# Motor_Double_Board.net
KiCad netlist of a schematic drawn in EAGLE
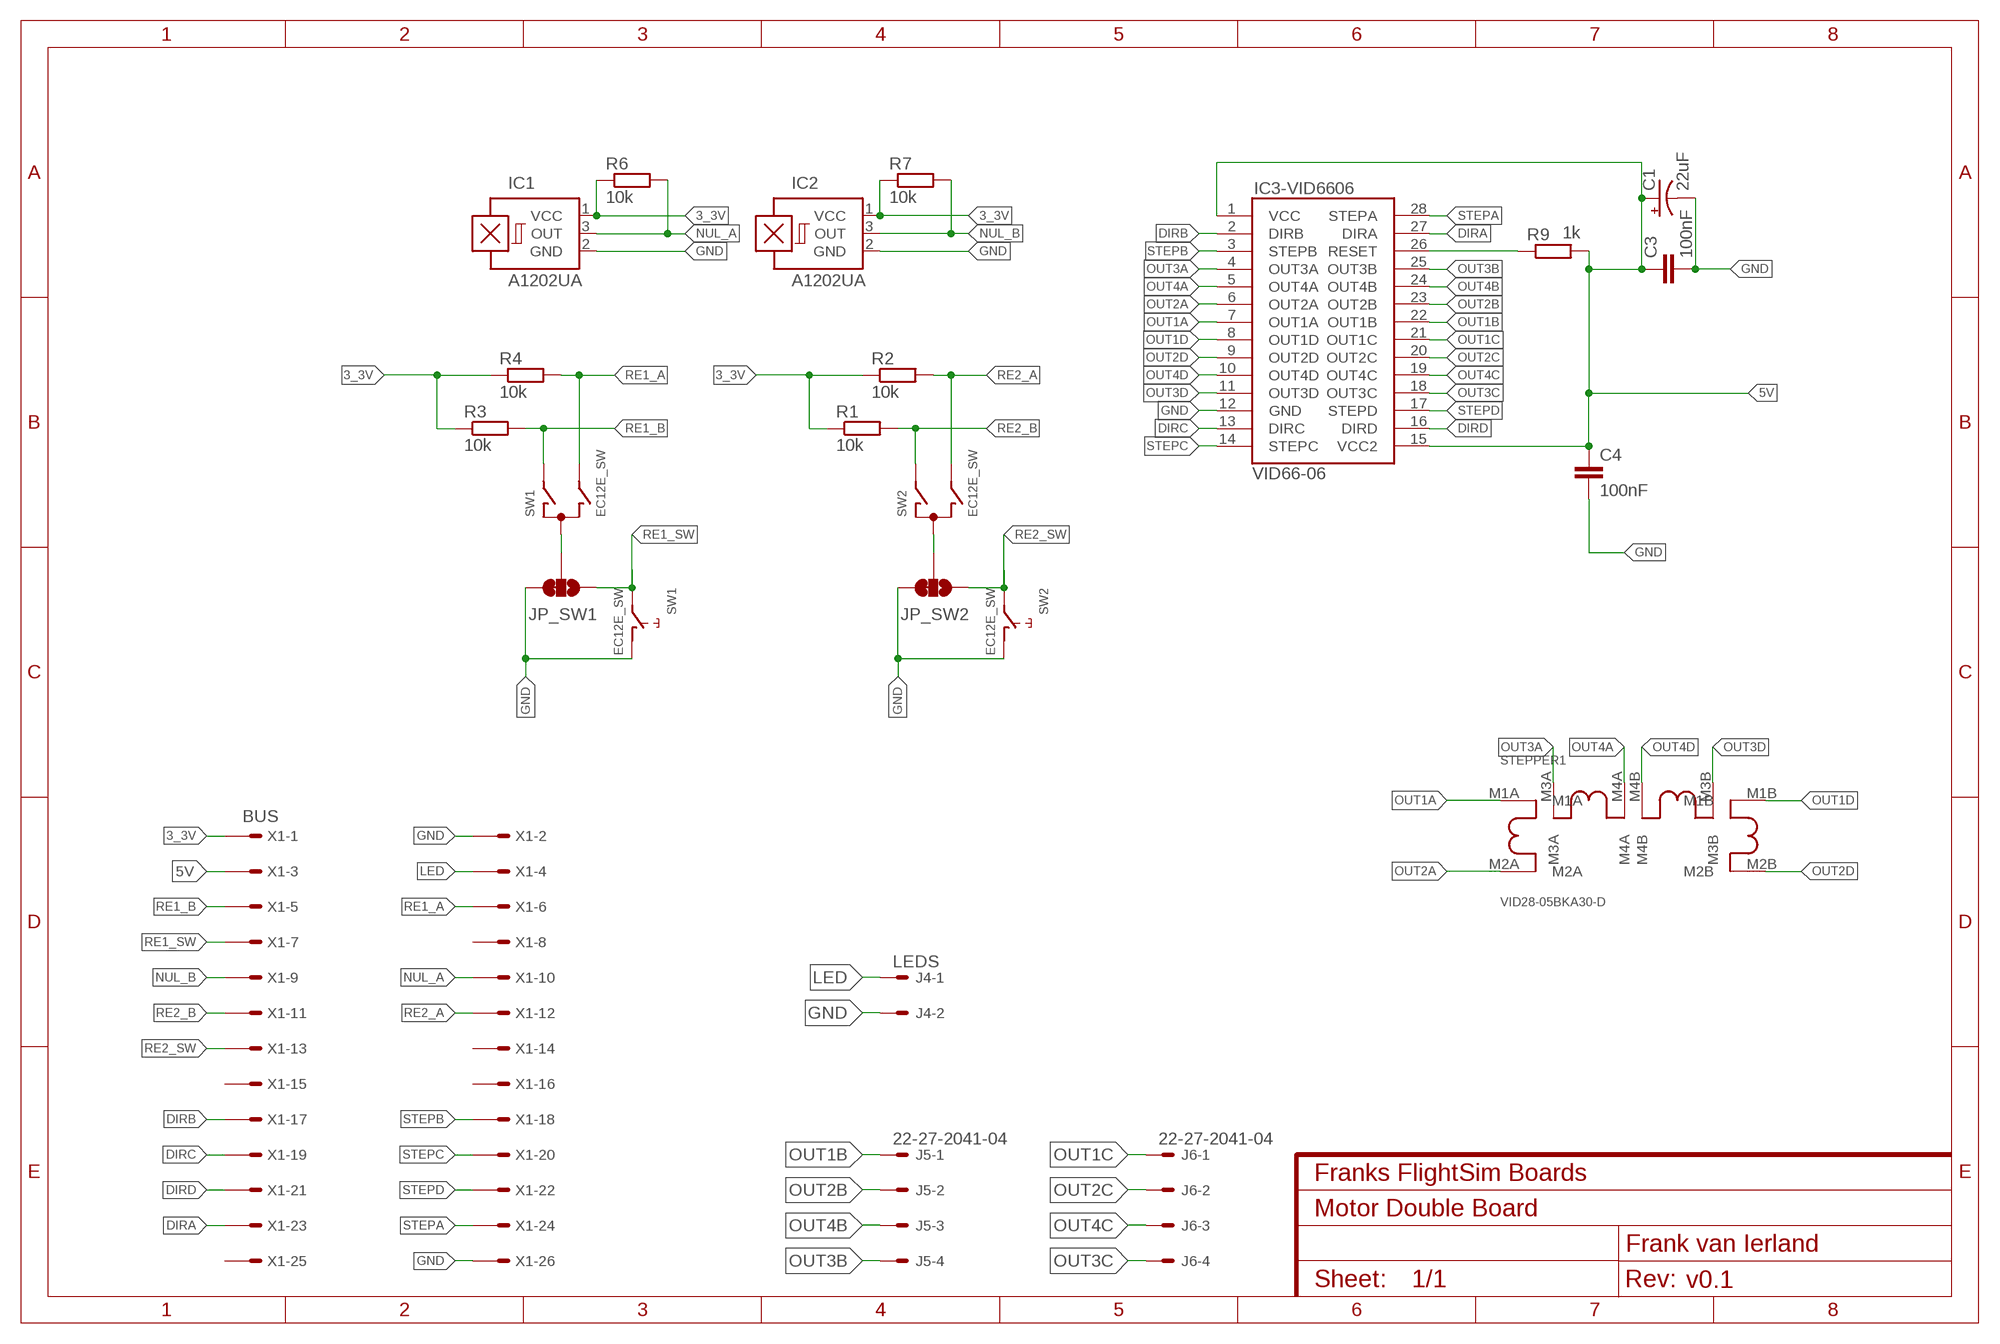
[diagram p0: schematic, sheet 1]

(export (version "E")
  (design (tool "Eeschema 10.0.6"))
  (components
    (comp (ref "C1")
      (value "22uF")
      (footprint "eagle-import:PANASONIC_C")
      (libsource (lib "eagle-import") (part "22UF-POLAR-PANASONIC_C-35V-20%"))
    )
    (comp (ref "C3")
      (value "100nF")
      (footprint "eagle-import:C0805")
      (libsource (lib "eagle-import") (part "C-EUC0805"))
    )
    (comp (ref "C4")
      (value "100nF")
      (footprint "eagle-import:C0805")
      (libsource (lib "eagle-import") (part "C-EUC0805"))
    )
    (comp (ref "IC1")
      (value "A1202UA")
      (footprint "eagle-import:SIP3-UA")
      (libsource (lib "eagle-import") (part "A12?UA02"))
    )
    (comp (ref "IC2")
      (value "A1202UA")
      (footprint "eagle-import:SIP3-UA")
      (libsource (lib "eagle-import") (part "A12?UA02"))
    )
    (comp (ref "IC3-VID6606")
      (value "VID66-06")
      (footprint "eagle-import:SO28W")
      (libsource (lib "eagle-import") (part "VID66-06"))
    )
    (comp (ref "J4")
      (value "LEDS")
      (footprint "eagle-import:6410-02")
      (fields (field (name "MF") "MOLEX"))
      (libsource (lib "eagle-import") (part "22-?-0227-2021"))
    )
    (comp (ref "J5")
      (value "22-27-2041-04")
      (footprint "eagle-import:6410-04")
      (fields (field (name "MF") "MOLEX"))
      (libsource (lib "eagle-import") (part "22-?-0427-2041"))
    )
    (comp (ref "J6")
      (value "22-27-2041-04")
      (footprint "eagle-import:6410-04")
      (fields (field (name "MF") "MOLEX"))
      (libsource (lib "eagle-import") (part "22-?-0427-2041"))
    )
    (comp (ref "JP_SW1")
      (value "JUMPER-SMT_3_1-NC_TRACE_SILK")
      (footprint "eagle-import:SMT-JUMPER_3_1-NC_TRACE_SILK")
      (libsource (lib "eagle-import") (part "JUMPER-SMT_3_1-NC_TRACE_SILK"))
    )
    (comp (ref "JP_SW2")
      (value "JUMPER-SMT_3_1-NC_TRACE_SILK")
      (footprint "eagle-import:SMT-JUMPER_3_1-NC_TRACE_SILK")
      (libsource (lib "eagle-import") (part "JUMPER-SMT_3_1-NC_TRACE_SILK"))
    )
    (comp (ref "R1")
      (value "10k")
      (footprint "eagle-import:M1206")
      (libsource (lib "eagle-import") (part "R-EU_M1206"))
    )
    (comp (ref "R2")
      (value "10k")
      (footprint "eagle-import:M1206")
      (libsource (lib "eagle-import") (part "R-EU_M1206"))
    )
    (comp (ref "R3")
      (value "10k")
      (footprint "eagle-import:M1206")
      (libsource (lib "eagle-import") (part "R-EU_M1206"))
    )
    (comp (ref "R4")
      (value "10k")
      (footprint "eagle-import:M1206")
      (libsource (lib "eagle-import") (part "R-EU_M1206"))
    )
    (comp (ref "R6")
      (value "10k")
      (footprint "eagle-import:M1206")
      (libsource (lib "eagle-import") (part "R-EU_M1206"))
    )
    (comp (ref "R7")
      (value "10k")
      (footprint "eagle-import:M1206")
      (libsource (lib "eagle-import") (part "R-EU_M1206"))
    )
    (comp (ref "R9")
      (value "1k")
      (footprint "eagle-import:M1206")
      (libsource (lib "eagle-import") (part "R-EU_M1206"))
    )
    (comp (ref "STEPPER1")
      (value "VID28-05BKA30-D")
      (footprint "eagle-import:BKA30D-R5-BACK-DUAL")
      (libsource (lib "eagle-import") (part "VID28-05BKA30-D"))
    )
    (comp (ref "SW1")
      (value "EC12E_SW")
      (footprint "eagle-import:ALPS_EC12E_SW")
      (fields (field (name "MPN") "EC12E2424407"))
      (libsource (lib "eagle-import") (part "EC12E_SW"))
    )
    (comp (ref "SW2")
      (value "EC12E_SW")
      (footprint "eagle-import:ALPS_EC12E_SW")
      (fields (field (name "MPN") "EC12E2424407"))
      (libsource (lib "eagle-import") (part "EC12E_SW"))
    )
    (comp (ref "X1")
      (value "BUS")
      (footprint "eagle-import:057-026-1")
      (libsource (lib "eagle-import") (part "057-026-1"))
    )
  )
  (nets
    (net (code "1") (name "3_3V") (class "Default")
      (node (ref "IC1") (pin "1") (pinfunction "VCC_1") (pintype "power_in"))
      (node (ref "IC2") (pin "1") (pinfunction "VCC_1") (pintype "power_in"))
      (node (ref "R1") (pin "1") (pinfunction "1_1") (pintype "passive"))
      (node (ref "R2") (pin "1") (pinfunction "1_1") (pintype "passive"))
      (node (ref "R3") (pin "1") (pinfunction "1_1") (pintype "passive"))
      (node (ref "R4") (pin "1") (pinfunction "1_1") (pintype "passive"))
      (node (ref "R6") (pin "1") (pinfunction "1_1") (pintype "passive"))
      (node (ref "R7") (pin "1") (pinfunction "1_1") (pintype "passive"))
      (node (ref "X1") (pin "1") (pinfunction "S_1") (pintype "passive"))
    )
    (net (code "2") (name "5V") (class "Default")
      (node (ref "C1") (pin "+") (pinfunction "+_+") (pintype "passive"))
      (node (ref "C3") (pin "1") (pinfunction "1_1") (pintype "passive"))
      (node (ref "C4") (pin "1") (pinfunction "1_1") (pintype "passive"))
      (node (ref "IC3-VID6606") (pin "1") (pinfunction "VCC_1") (pintype "power_in"))
      (node (ref "IC3-VID6606") (pin "15") (pinfunction "VCC2_15") (pintype "power_in"))
      (node (ref "R9") (pin "2") (pinfunction "2_2") (pintype "passive"))
      (node (ref "X1") (pin "3") (pinfunction "S_3") (pintype "passive"))
    )
    (net (code "3") (name "DIRA") (class "Default")
      (node (ref "IC3-VID6606") (pin "27") (pinfunction "DIRA_27") (pintype "input"))
      (node (ref "X1") (pin "23") (pinfunction "S_23") (pintype "passive"))
    )
    (net (code "4") (name "DIRB") (class "Default")
      (node (ref "IC3-VID6606") (pin "2") (pinfunction "DIRB_2") (pintype "input"))
      (node (ref "X1") (pin "17") (pinfunction "S_17") (pintype "passive"))
    )
    (net (code "5") (name "DIRC") (class "Default")
      (node (ref "IC3-VID6606") (pin "13") (pinfunction "DIRC_13") (pintype "input"))
      (node (ref "X1") (pin "19") (pinfunction "S_19") (pintype "passive"))
    )
    (net (code "6") (name "DIRD") (class "Default")
      (node (ref "IC3-VID6606") (pin "16") (pinfunction "DIRD_16") (pintype "input"))
      (node (ref "X1") (pin "21") (pinfunction "S_21") (pintype "passive"))
    )
    (net (code "7") (name "GND") (class "Default")
      (node (ref "C1") (pin "-") (pinfunction "-_-") (pintype "passive"))
      (node (ref "C3") (pin "2") (pinfunction "2_2") (pintype "passive"))
      (node (ref "C4") (pin "2") (pinfunction "2_2") (pintype "passive"))
      (node (ref "IC1") (pin "2") (pinfunction "GND_2") (pintype "power_in"))
      (node (ref "IC2") (pin "2") (pinfunction "GND_2") (pintype "power_in"))
      (node (ref "IC3-VID6606") (pin "12") (pinfunction "GND_12") (pintype "power_in"))
      (node (ref "J4") (pin "2") (pinfunction "S_2") (pintype "passive"))
      (node (ref "JP_SW1") (pin "3") (pinfunction "3_3") (pintype "passive"))
      (node (ref "JP_SW2") (pin "3") (pinfunction "3_3") (pintype "passive"))
      (node (ref "SW1") (pin "D") (pinfunction "1_D") (pintype "passive"))
      (node (ref "SW2") (pin "D") (pinfunction "1_D") (pintype "passive"))
      (node (ref "X1") (pin "2") (pinfunction "S_2") (pintype "passive"))
      (node (ref "X1") (pin "26") (pinfunction "S_26") (pintype "passive"))
    )
    (net (code "8") (name "LED") (class "Default")
      (node (ref "J4") (pin "1") (pinfunction "S_1") (pintype "passive"))
      (node (ref "X1") (pin "4") (pinfunction "S_4") (pintype "passive"))
    )
    (net (code "9") (name "NUL_A") (class "Default")
      (node (ref "IC1") (pin "3") (pinfunction "OUT_3") (pintype "output"))
      (node (ref "R6") (pin "2") (pinfunction "2_2") (pintype "passive"))
      (node (ref "X1") (pin "10") (pinfunction "S_10") (pintype "passive"))
    )
    (net (code "10") (name "NUL_B") (class "Default")
      (node (ref "IC2") (pin "3") (pinfunction "OUT_3") (pintype "output"))
      (node (ref "R7") (pin "2") (pinfunction "2_2") (pintype "passive"))
      (node (ref "X1") (pin "9") (pinfunction "S_9") (pintype "passive"))
    )
    (net (code "11") (name "Net-(IC3-VID6606-RESET)") (class "Default")
      (node (ref "IC3-VID6606") (pin "26") (pinfunction "RESET_26") (pintype "input"))
      (node (ref "R9") (pin "1") (pinfunction "1_1") (pintype "passive"))
    )
    (net (code "12") (name "Net-(JP_SW1-Pad2)") (class "Default")
      (node (ref "JP_SW1") (pin "2") (pinfunction "2_2") (pintype "passive"))
      (node (ref "SW1") (pin "C") (pinfunction "C_C") (pintype "passive"))
    )
    (net (code "13") (name "Net-(JP_SW2-Pad2)") (class "Default")
      (node (ref "JP_SW2") (pin "2") (pinfunction "2_2") (pintype "passive"))
      (node (ref "SW2") (pin "C") (pinfunction "C_C") (pintype "passive"))
    )
    (net (code "14") (name "OUT1A") (class "Default")
      (node (ref "IC3-VID6606") (pin "7") (pinfunction "OUT1A_7") (pintype "output"))
      (node (ref "STEPPER1") (pin "M1A") (pinfunction "M1A_M1A") (pintype "input"))
    )
    (net (code "15") (name "OUT1B") (class "Default")
      (node (ref "IC3-VID6606") (pin "22") (pinfunction "OUT1B_22") (pintype "output"))
      (node (ref "J5") (pin "1") (pinfunction "S_1") (pintype "passive"))
    )
    (net (code "16") (name "OUT1C") (class "Default")
      (node (ref "IC3-VID6606") (pin "21") (pinfunction "OUT1C_21") (pintype "output"))
      (node (ref "J6") (pin "1") (pinfunction "S_1") (pintype "passive"))
    )
    (net (code "17") (name "OUT1D") (class "Default")
      (node (ref "IC3-VID6606") (pin "8") (pinfunction "OUT1D_8") (pintype "output"))
      (node (ref "STEPPER1") (pin "M1B") (pinfunction "M1B_M1B") (pintype "bidirectional"))
    )
    (net (code "18") (name "OUT2A") (class "Default")
      (node (ref "IC3-VID6606") (pin "6") (pinfunction "OUT2A_6") (pintype "output"))
      (node (ref "STEPPER1") (pin "M2A") (pinfunction "M2A_M2A") (pintype "input"))
    )
    (net (code "19") (name "OUT2B") (class "Default")
      (node (ref "IC3-VID6606") (pin "23") (pinfunction "OUT2B_23") (pintype "output"))
      (node (ref "J5") (pin "2") (pinfunction "S_2") (pintype "passive"))
    )
    (net (code "20") (name "OUT2C") (class "Default")
      (node (ref "IC3-VID6606") (pin "20") (pinfunction "OUT2C_20") (pintype "output"))
      (node (ref "J6") (pin "2") (pinfunction "S_2") (pintype "passive"))
    )
    (net (code "21") (name "OUT2D") (class "Default")
      (node (ref "IC3-VID6606") (pin "9") (pinfunction "OUT2D_9") (pintype "output"))
      (node (ref "STEPPER1") (pin "M2B") (pinfunction "M2B_M2B") (pintype "input"))
    )
    (net (code "22") (name "OUT3A") (class "Default")
      (node (ref "IC3-VID6606") (pin "4") (pinfunction "OUT3A_4") (pintype "output"))
      (node (ref "STEPPER1") (pin "M3A") (pinfunction "M3A_M3A") (pintype "input"))
    )
    (net (code "23") (name "OUT3B") (class "Default")
      (node (ref "IC3-VID6606") (pin "25") (pinfunction "OUT3B_25") (pintype "output"))
      (node (ref "J5") (pin "4") (pinfunction "S_4") (pintype "passive"))
    )
    (net (code "24") (name "OUT3C") (class "Default")
      (node (ref "IC3-VID6606") (pin "18") (pinfunction "OUT3C_18") (pintype "output"))
      (node (ref "J6") (pin "4") (pinfunction "S_4") (pintype "passive"))
    )
    (net (code "25") (name "OUT3D") (class "Default")
      (node (ref "IC3-VID6606") (pin "11") (pinfunction "OUT3D_11") (pintype "output"))
      (node (ref "STEPPER1") (pin "M3B") (pinfunction "M3B_M3B") (pintype "bidirectional"))
    )
    (net (code "26") (name "OUT4A") (class "Default")
      (node (ref "IC3-VID6606") (pin "5") (pinfunction "OUT4A_5") (pintype "output"))
      (node (ref "STEPPER1") (pin "M4A") (pinfunction "M4A_M4A") (pintype "input"))
    )
    (net (code "27") (name "OUT4B") (class "Default")
      (node (ref "IC3-VID6606") (pin "24") (pinfunction "OUT4B_24") (pintype "output"))
      (node (ref "J5") (pin "3") (pinfunction "S_3") (pintype "passive"))
    )
    (net (code "28") (name "OUT4C") (class "Default")
      (node (ref "IC3-VID6606") (pin "19") (pinfunction "OUT4C_19") (pintype "output"))
      (node (ref "J6") (pin "3") (pinfunction "S_3") (pintype "passive"))
    )
    (net (code "29") (name "OUT4D") (class "Default")
      (node (ref "IC3-VID6606") (pin "10") (pinfunction "OUT4D_10") (pintype "output"))
      (node (ref "STEPPER1") (pin "M4B") (pinfunction "M4B_M4B") (pintype "bidirectional"))
    )
    (net (code "30") (name "RE1_A") (class "Default")
      (node (ref "R4") (pin "2") (pinfunction "2_2") (pintype "passive"))
      (node (ref "SW1") (pin "B") (pinfunction "B_B") (pintype "passive"))
      (node (ref "X1") (pin "6") (pinfunction "S_6") (pintype "passive"))
    )
    (net (code "31") (name "RE1_B") (class "Default")
      (node (ref "R3") (pin "2") (pinfunction "2_2") (pintype "passive"))
      (node (ref "SW1") (pin "A") (pinfunction "A_A") (pintype "passive"))
      (node (ref "X1") (pin "5") (pinfunction "S_5") (pintype "passive"))
    )
    (net (code "32") (name "RE1_SW") (class "Default")
      (node (ref "JP_SW1") (pin "1") (pinfunction "1_1") (pintype "passive"))
      (node (ref "SW1") (pin "E") (pinfunction "2_E") (pintype "passive"))
      (node (ref "X1") (pin "7") (pinfunction "S_7") (pintype "passive"))
    )
    (net (code "33") (name "RE2_A") (class "Default")
      (node (ref "R2") (pin "2") (pinfunction "2_2") (pintype "passive"))
      (node (ref "SW2") (pin "B") (pinfunction "B_B") (pintype "passive"))
      (node (ref "X1") (pin "12") (pinfunction "S_12") (pintype "passive"))
    )
    (net (code "34") (name "RE2_B") (class "Default")
      (node (ref "R1") (pin "2") (pinfunction "2_2") (pintype "passive"))
      (node (ref "SW2") (pin "A") (pinfunction "A_A") (pintype "passive"))
      (node (ref "X1") (pin "11") (pinfunction "S_11") (pintype "passive"))
    )
    (net (code "35") (name "RE2_SW") (class "Default")
      (node (ref "JP_SW2") (pin "1") (pinfunction "1_1") (pintype "passive"))
      (node (ref "SW2") (pin "E") (pinfunction "2_E") (pintype "passive"))
      (node (ref "X1") (pin "13") (pinfunction "S_13") (pintype "passive"))
    )
    (net (code "36") (name "STEPA") (class "Default")
      (node (ref "IC3-VID6606") (pin "28") (pinfunction "STEPA_28") (pintype "input"))
      (node (ref "X1") (pin "24") (pinfunction "S_24") (pintype "passive"))
    )
    (net (code "37") (name "STEPB") (class "Default")
      (node (ref "IC3-VID6606") (pin "3") (pinfunction "STEPB_3") (pintype "input"))
      (node (ref "X1") (pin "18") (pinfunction "S_18") (pintype "passive"))
    )
    (net (code "38") (name "STEPC") (class "Default")
      (node (ref "IC3-VID6606") (pin "14") (pinfunction "STEPC_14") (pintype "input"))
      (node (ref "X1") (pin "20") (pinfunction "S_20") (pintype "passive"))
    )
    (net (code "39") (name "STEPD") (class "Default")
      (node (ref "IC3-VID6606") (pin "17") (pinfunction "STEPD_17") (pintype "input"))
      (node (ref "X1") (pin "22") (pinfunction "S_22") (pintype "passive"))
    )
    (net (code "40") (name "unconnected-(X1F-S-Pad14)") (class "Default")
      (node (ref "X1") (pin "14") (pinfunction "S_14") (pintype "passive"))
    )
    (net (code "41") (name "unconnected-(X1G-S-Pad15)") (class "Default")
      (node (ref "X1") (pin "15") (pinfunction "S_15") (pintype "passive"))
    )
    (net (code "42") (name "unconnected-(X1H-S-Pad16)") (class "Default")
      (node (ref "X1") (pin "16") (pinfunction "S_16") (pintype "passive"))
    )
    (net (code "43") (name "unconnected-(X1R-S-Pad25)") (class "Default")
      (node (ref "X1") (pin "25") (pinfunction "S_25") (pintype "passive"))
    )
    (net (code "44") (name "unconnected-(X1Y-S-Pad8)") (class "Default")
      (node (ref "X1") (pin "8") (pinfunction "S_8") (pintype "passive"))
    )
  )
)
